# smartstickSTM32f103cb.net
KiCad netlist of a schematic drawn in EAGLE
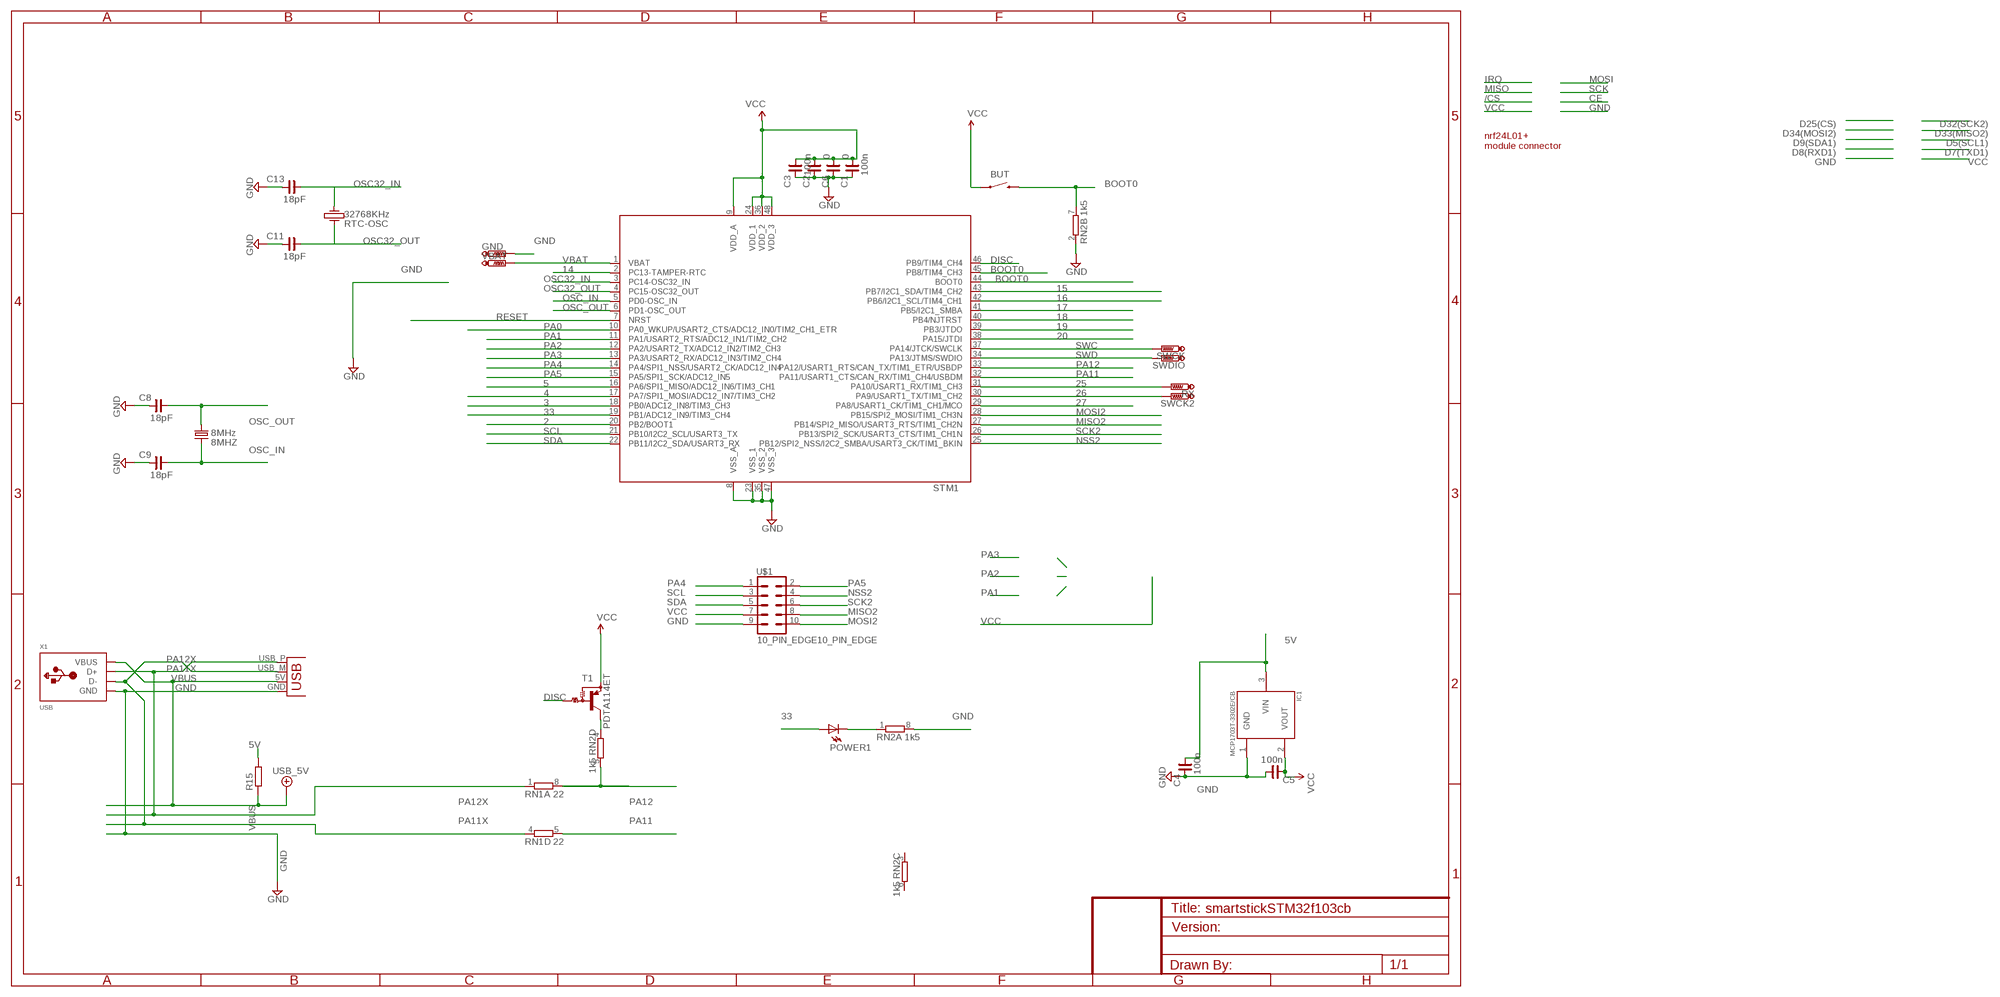
[diagram p0: schematic, sheet 1]

(export (version "E")
  (design (tool "Eeschema 10.0.6"))
  (components
    (comp (ref "8MHZ")
      (value "8MHz")
      (footprint "eagle-import:HC49US")
      (libsource (lib "eagle-import") (part "CRYSTALHC49US"))
    )
    (comp (ref "BUT")
      (value "SWITCH-MOMENTARY-2-SMD-1101NE")
      (footprint "eagle-import:TACTILE-SWITCH-1101NE")
      (libsource (lib "eagle-import") (part "SWITCH-MOMENTARY-2-SMD-1101NE"))
    )
    (comp (ref "C1")
      (value "100n")
      (footprint "eagle-import:C0603")
      (libsource (lib "eagle-import") (part "C_0603"))
    )
    (comp (ref "C2")
      (value "0")
      (footprint "eagle-import:C0603")
      (libsource (lib "eagle-import") (part "C_0603"))
    )
    (comp (ref "C3")
      (value "100n")
      (footprint "eagle-import:C0603")
      (libsource (lib "eagle-import") (part "C_0603"))
    )
    (comp (ref "C4")
      (value "100n")
      (footprint "eagle-import:C0603")
      (libsource (lib "eagle-import") (part "C_0603"))
    )
    (comp (ref "C5")
      (value "100n")
      (footprint "eagle-import:C0603")
      (libsource (lib "eagle-import") (part "C_0603"))
    )
    (comp (ref "C6")
      (value "0")
      (footprint "eagle-import:C0603")
      (libsource (lib "eagle-import") (part "C_0603"))
    )
    (comp (ref "C8")
      (value "18pF")
      (footprint "eagle-import:C0603")
      (libsource (lib "eagle-import") (part "C_0603"))
    )
    (comp (ref "C9")
      (value "18pF")
      (footprint "eagle-import:C0603")
      (libsource (lib "eagle-import") (part "C_0603"))
    )
    (comp (ref "C11")
      (value "18pF")
      (footprint "eagle-import:C0603")
      (libsource (lib "eagle-import") (part "C_0603"))
    )
    (comp (ref "C13")
      (value "18pF")
      (footprint "eagle-import:C0603")
      (libsource (lib "eagle-import") (part "C_0603"))
    )
    (comp (ref "GND")
      (value "PTR1TP20SQ")
      (footprint "eagle-import:TP20SQ")
      (libsource (lib "eagle-import") (part "PTR1TP20SQ"))
    )
    (comp (ref "IC1")
      (value "MCP1703T-3302E/CB")
      (footprint "eagle-import:SOT23")
      (libsource (lib "eagle-import") (part "MCP1700T"))
    )
    (comp (ref "POWER1")
      (value "Power")
      (footprint "eagle-import:LED-0603")
      (libsource (lib "eagle-import") (part "LED0603"))
    )
    (comp (ref "R15")
      (value "R-EU_R0603")
      (footprint "eagle-import:R0603")
      (libsource (lib "eagle-import") (part "R-EU_R0603"))
    )
    (comp (ref "RN1")
      (value "22")
      (footprint "eagle-import:0603-ARC")
      (libsource (lib "eagle-import") (part "4R-N0603-ARC"))
    )
    (comp (ref "RN2")
      (value "1k5")
      (footprint "eagle-import:0603-ARC")
      (libsource (lib "eagle-import") (part "4R-N0603-ARC"))
    )
    (comp (ref "RTC-OSC")
      (value "32768KHz")
      (footprint "eagle-import:KX-327LT")
      (libsource (lib "eagle-import") (part "CRYSTALL"))
    )
    (comp (ref "RX")
      (value "PTR1TP10R")
      (footprint "eagle-import:TP10R")
      (libsource (lib "eagle-import") (part "PTR1TP10R"))
    )
    (comp (ref "STM1")
      (value "STM32F103CB")
      (footprint "eagle-import:LQFP48")
      (libsource (lib "eagle-import") (part "STM32F103CB"))
    )
    (comp (ref "SWCK")
      (value "PTR1TP16R")
      (footprint "eagle-import:TP16R")
      (libsource (lib "eagle-import") (part "PTR1TP16R"))
    )
    (comp (ref "SWCK2")
      (value "PTR1TP10R")
      (footprint "eagle-import:TP10R")
      (libsource (lib "eagle-import") (part "PTR1TP10R"))
    )
    (comp (ref "SWDIO")
      (value "PTR1TP16R")
      (footprint "eagle-import:TP16R")
      (libsource (lib "eagle-import") (part "PTR1TP16R"))
    )
    (comp (ref "T1")
      (value "PDTA114ET")
      (footprint "eagle-import:ES_SOT23-3")
      (libsource (lib "eagle-import") (part "ES_PNP-DRIVERSOT23-3"))
    )
    (comp (ref "U$1")
      (value "10_PIN_EDGE10_PIN_EDGE")
      (footprint "eagle-import:10_PIN_EDGE")
      (libsource (lib "eagle-import") (part "10_PIN_EDGE10_PIN_EDGE"))
    )
    (comp (ref "VBAT")
      (value "PTR1TP19R")
      (footprint "eagle-import:TP19R")
      (libsource (lib "eagle-import") (part "PTR1TP19R"))
    )
    (comp (ref "X1")
      (value "USB")
      (footprint "eagle-import:MOLEX-48037-1000")
      (libsource (lib "eagle-import") (part "USB"))
    )
    (comp (ref "X3")
      (value "USBPCB")
      (footprint "eagle-import:USB-A-PCB")
      (libsource (lib "eagle-import") (part "USBPCB"))
    )
  )
  (nets
    (net (code "1") (name "/2") (class "Default")
      (node (ref "STM1") (pin "20") (pinfunction "PB2/BOOT1_20") (pintype "bidirectional"))
    )
    (net (code "2") (name "/3") (class "Default")
      (node (ref "STM1") (pin "18") (pinfunction "PB0/ADC12_IN8/TIM3_CH3_18") (pintype "bidirectional"))
    )
    (net (code "3") (name "/4") (class "Default")
      (node (ref "STM1") (pin "17") (pinfunction "PA7/SPI1_MOSI/ADC12_IN7/TIM3_CH2_17") (pintype "bidirectional"))
    )
    (net (code "4") (name "/5") (class "Default")
      (node (ref "STM1") (pin "16") (pinfunction "PA6/SPI1_MISO/ADC12_IN6/TIM3_CH1_16") (pintype "bidirectional"))
    )
    (net (code "5") (name "/5V") (class "Default")
      (node (ref "C4") (pin "1") (pinfunction "1_1") (pintype "passive"))
      (node (ref "IC1") (pin "3") (pinfunction "VIN_3") (pintype "bidirectional"))
      (node (ref "R15") (pin "2") (pinfunction "2_2") (pintype "passive"))
    )
    (net (code "6") (name "/14") (class "Default")
      (node (ref "STM1") (pin "2") (pinfunction "PC13-TAMPER-RTC_2") (pintype "input"))
    )
    (net (code "7") (name "/15") (class "Default")
      (node (ref "STM1") (pin "43") (pinfunction "PB7/I2C1_SDA/TIM4_CH2_43") (pintype "bidirectional"))
    )
    (net (code "8") (name "/16") (class "Default")
      (node (ref "STM1") (pin "42") (pinfunction "PB6/I2C1_SCL/TIM4_CH1_42") (pintype "input"))
    )
    (net (code "9") (name "/17") (class "Default")
      (node (ref "STM1") (pin "41") (pinfunction "PB5/I2C1_SMBA_41") (pintype "input"))
    )
    (net (code "10") (name "/18") (class "Default")
      (node (ref "STM1") (pin "40") (pinfunction "PB4/NJTRST_40") (pintype "bidirectional"))
    )
    (net (code "11") (name "/19") (class "Default")
      (node (ref "STM1") (pin "39") (pinfunction "PB3/JTDO_39") (pintype "bidirectional"))
    )
    (net (code "12") (name "/20") (class "Default")
      (node (ref "STM1") (pin "38") (pinfunction "PA15/JTDI_38") (pintype "bidirectional"))
    )
    (net (code "13") (name "/25") (class "Default")
      (node (ref "RX") (pin "TP") (pinfunction "TP_TP") (pintype "input"))
      (node (ref "STM1") (pin "31") (pinfunction "PA10/USART1_RX/TIM1_CH3_31") (pintype "bidirectional"))
    )
    (net (code "14") (name "/26") (class "Default")
      (node (ref "STM1") (pin "30") (pinfunction "PA9/USART1_TX/TIM1_CH2_30") (pintype "input"))
      (node (ref "SWCK2") (pin "TP") (pinfunction "TP_TP") (pintype "input"))
    )
    (net (code "15") (name "/27") (class "Default")
      (node (ref "STM1") (pin "29") (pinfunction "PA8/USART1_CK/TIM1_CH1/MCO_29") (pintype "bidirectional"))
    )
    (net (code "16") (name "/33") (class "Default")
      (node (ref "POWER1") (pin "A") (pinfunction "A_A") (pintype "passive"))
      (node (ref "STM1") (pin "19") (pinfunction "PB1/ADC12_IN9/TIM3_CH4_19") (pintype "bidirectional"))
    )
    (net (code "17") (name "/BOOT0") (class "Default")
      (node (ref "BUT") (pin "P$2") (pinfunction "2_P$2") (pintype "passive"))
      (node (ref "RN2") (pin "7") (pinfunction "2_7") (pintype "passive"))
      (node (ref "STM1") (pin "44") (pinfunction "BOOT0_44") (pintype "input"))
      (node (ref "STM1") (pin "45") (pinfunction "PB8/TIM4_CH3_45") (pintype "bidirectional"))
    )
    (net (code "27") (name "/DISC") (class "Default")
      (node (ref "STM1") (pin "46") (pinfunction "PB9/TIM4_CH4_46") (pintype "input"))
      (node (ref "T1") (pin "1") (pinfunction "B_1") (pintype "passive"))
    )
    (net (code "30") (name "/MISO2") (class "Default")
      (node (ref "STM1") (pin "27") (pinfunction "PB14/SPI2_MISO/USART3_RTS/TIM1_CH2N_27") (pintype "input"))
      (node (ref "U$1") (pin "8") (pinfunction "8_8") (pintype "passive"))
    )
    (net (code "32") (name "/MOSI2") (class "Default")
      (node (ref "STM1") (pin "28") (pinfunction "PB15/SPI2_MOSI/TIM1_CH3N_28") (pintype "input"))
      (node (ref "U$1") (pin "10") (pinfunction "10_10") (pintype "passive"))
    )
    (net (code "33") (name "/NSS2") (class "Default")
      (node (ref "STM1") (pin "25") (pinfunction "PB12/SPI2_NSS/I2C2_SMBA/USART3_CK/TIM1_BKIN_25") (pintype "input"))
      (node (ref "U$1") (pin "4") (pinfunction "4_4") (pintype "passive"))
    )
    (net (code "34") (name "/OSC32_IN") (class "Default")
      (node (ref "C13") (pin "1") (pinfunction "1_1") (pintype "passive"))
      (node (ref "RTC-OSC") (pin "1") (pinfunction "P$1_1") (pintype "bidirectional"))
      (node (ref "STM1") (pin "3") (pinfunction "PC14-OSC32_IN_3") (pintype "input"))
    )
    (net (code "35") (name "/OSC32_OUT") (class "Default")
      (node (ref "C11") (pin "1") (pinfunction "1_1") (pintype "passive"))
      (node (ref "RTC-OSC") (pin "4") (pinfunction "P$2_4") (pintype "bidirectional"))
      (node (ref "STM1") (pin "4") (pinfunction "PC15-OSC32_OUT_4") (pintype "input"))
    )
    (net (code "36") (name "/OSC_IN") (class "Default")
      (node (ref "8MHZ") (pin "2") (pinfunction "2_2") (pintype "passive"))
      (node (ref "C9") (pin "1") (pinfunction "1_1") (pintype "passive"))
      (node (ref "STM1") (pin "5") (pinfunction "PD0-OSC_IN_5") (pintype "input"))
    )
    (net (code "37") (name "/OSC_OUT") (class "Default")
      (node (ref "8MHZ") (pin "1") (pinfunction "1_1") (pintype "passive"))
      (node (ref "C8") (pin "1") (pinfunction "1_1") (pintype "passive"))
      (node (ref "STM1") (pin "6") (pinfunction "PD1-OSC_OUT_6") (pintype "input"))
    )
    (net (code "38") (name "/PA0") (class "Default")
      (node (ref "STM1") (pin "10") (pinfunction "PA0_WKUP/USART2_CTS/ADC12_IN0/TIM2_CH1_ETR_10") (pintype "bidirectional"))
    )
    (net (code "39") (name "/PA1") (class "Default")
      (node (ref "STM1") (pin "11") (pinfunction "PA1/USART2_RTS/ADC12_IN1/TIM2_CH2_11") (pintype "bidirectional"))
    )
    (net (code "40") (name "/PA2") (class "Default")
      (node (ref "STM1") (pin "12") (pinfunction "PA2/USART2_TX/ADC12_IN2/TIM2_CH3_12") (pintype "bidirectional"))
    )
    (net (code "41") (name "/PA3") (class "Default")
      (node (ref "STM1") (pin "13") (pinfunction "PA3/USART2_RX/ADC12_IN3/TIM2_CH4_13") (pintype "bidirectional"))
    )
    (net (code "42") (name "/PA4") (class "Default")
      (node (ref "STM1") (pin "14") (pinfunction "PA4/SPI1_NSS/USART2_CK/ADC12_IN4_14") (pintype "bidirectional"))
      (node (ref "U$1") (pin "1") (pinfunction "1_1") (pintype "passive"))
    )
    (net (code "43") (name "/PA5") (class "Default")
      (node (ref "STM1") (pin "15") (pinfunction "PA5/SPI1_SCK/ADC12_IN5_15") (pintype "bidirectional"))
      (node (ref "U$1") (pin "2") (pinfunction "2_2") (pintype "passive"))
    )
    (net (code "44") (name "/PA11") (class "Default")
      (node (ref "RN1") (pin "5") (pinfunction "2_5") (pintype "passive"))
      (node (ref "STM1") (pin "32") (pinfunction "PA11/USART1_CTS/CAN_RX/TIM1_CH4/USBDM_32") (pintype "bidirectional"))
    )
    (net (code "45") (name "/PA11X") (class "Default")
      (node (ref "RN1") (pin "4") (pinfunction "1_4") (pintype "passive"))
      (node (ref "X1") (pin "2") (pinfunction "D-_2") (pintype "bidirectional"))
      (node (ref "X3") (pin "USB_M") (pinfunction "D-_USB_M") (pintype "bidirectional"))
    )
    (net (code "46") (name "/PA12") (class "Default")
      (node (ref "RN1") (pin "8") (pinfunction "2_8") (pintype "passive"))
      (node (ref "RN2") (pin "5") (pinfunction "2_5") (pintype "passive"))
      (node (ref "STM1") (pin "33") (pinfunction "PA12/USART1_RTS/CAN_TX/TIM1_ETR/USBDP_33") (pintype "bidirectional"))
    )
    (net (code "47") (name "/PA12X") (class "Default")
      (node (ref "RN1") (pin "1") (pinfunction "1_1") (pintype "passive"))
      (node (ref "X1") (pin "3") (pinfunction "D+_3") (pintype "bidirectional"))
      (node (ref "X3") (pin "USB_P") (pinfunction "D+_USB_P") (pintype "bidirectional"))
    )
    (net (code "48") (name "/RESET") (class "Default")
      (node (ref "STM1") (pin "7") (pinfunction "NRST_7") (pintype "input"))
    )
    (net (code "50") (name "/SCK2") (class "Default")
      (node (ref "STM1") (pin "26") (pinfunction "PB13/SPI2_SCK/USART3_CTS/TIM1_CH1N_26") (pintype "input"))
      (node (ref "U$1") (pin "6") (pinfunction "6_6") (pintype "passive"))
    )
    (net (code "51") (name "/SCL") (class "Default")
      (node (ref "STM1") (pin "21") (pinfunction "PB10/I2C2_SCL/USART3_TX_21") (pintype "input"))
      (node (ref "U$1") (pin "3") (pinfunction "3_3") (pintype "passive"))
    )
    (net (code "52") (name "/SDA") (class "Default")
      (node (ref "STM1") (pin "22") (pinfunction "PB11/I2C2_SDA/USART3_RX_22") (pintype "input"))
      (node (ref "U$1") (pin "5") (pinfunction "5_5") (pintype "passive"))
    )
    (net (code "53") (name "/SWC") (class "Default")
      (node (ref "STM1") (pin "37") (pinfunction "PA14/JTCK/SWCLK_37") (pintype "bidirectional"))
      (node (ref "SWCK") (pin "TP") (pinfunction "TP_TP") (pintype "input"))
    )
    (net (code "54") (name "/SWD") (class "Default")
      (node (ref "STM1") (pin "34") (pinfunction "PA13/JTMS/SWDIO_34") (pintype "bidirectional"))
      (node (ref "SWDIO") (pin "TP") (pinfunction "TP_TP") (pintype "input"))
    )
    (net (code "55") (name "/VBAT") (class "Default")
      (node (ref "STM1") (pin "1") (pinfunction "VBAT_1") (pintype "power_in"))
      (node (ref "VBAT") (pin "TP") (pinfunction "TP_TP") (pintype "input"))
    )
    (net (code "57") (name "GND") (class "Default")
      (node (ref "C1") (pin "2") (pinfunction "2_2") (pintype "passive"))
      (node (ref "C11") (pin "2") (pinfunction "2_2") (pintype "passive"))
      (node (ref "C13") (pin "2") (pinfunction "2_2") (pintype "passive"))
      (node (ref "C2") (pin "2") (pinfunction "2_2") (pintype "passive"))
      (node (ref "C3") (pin "2") (pinfunction "2_2") (pintype "passive"))
      (node (ref "C4") (pin "2") (pinfunction "2_2") (pintype "passive"))
      (node (ref "C5") (pin "1") (pinfunction "1_1") (pintype "passive"))
      (node (ref "C6") (pin "2") (pinfunction "2_2") (pintype "passive"))
      (node (ref "C8") (pin "2") (pinfunction "2_2") (pintype "passive"))
      (node (ref "C9") (pin "2") (pinfunction "2_2") (pintype "passive"))
      (node (ref "GND") (pin "TP") (pinfunction "TP_TP") (pintype "input"))
      (node (ref "IC1") (pin "1") (pinfunction "GND_1") (pintype "bidirectional"))
      (node (ref "RN2") (pin "2") (pinfunction "1_2") (pintype "passive"))
      (node (ref "RN2") (pin "8") (pinfunction "2_8") (pintype "passive"))
      (node (ref "STM1") (pin "23") (pinfunction "VSS_1_23") (pintype "power_in"))
      (node (ref "STM1") (pin "35") (pinfunction "VSS_2_35") (pintype "power_in"))
      (node (ref "STM1") (pin "47") (pinfunction "VSS_3_47") (pintype "power_in"))
      (node (ref "STM1") (pin "8") (pinfunction "VSS_A_8") (pintype "power_in"))
      (node (ref "U$1") (pin "9") (pinfunction "9_9") (pintype "passive"))
      (node (ref "X1") (pin "4") (pinfunction "GND_4") (pintype "power_in"))
      (node (ref "X3") (pin "GND") (pinfunction "GND_GND") (pintype "bidirectional"))
    )
    (net (code "58") (name "Net-(POWER1-PadC)") (class "Default")
      (node (ref "POWER1") (pin "C") (pinfunction "C_C") (pintype "passive"))
      (node (ref "RN2") (pin "1") (pinfunction "1_1") (pintype "passive"))
    )
    (net (code "59") (name "Net-(RN2D-1)") (class "Default")
      (node (ref "RN2") (pin "4") (pinfunction "1_4") (pintype "passive"))
      (node (ref "T1") (pin "3") (pinfunction "C_3") (pintype "passive"))
    )
    (net (code "60") (name "USB_5V") (class "Default")
      (node (ref "R15") (pin "1") (pinfunction "1_1") (pintype "passive"))
      (node (ref "X1") (pin "1") (pinfunction "VBUS_1") (pintype "power_in"))
      (node (ref "X3") (pin "5V") (pinfunction "VBUS_5V") (pintype "bidirectional"))
    )
    (net (code "61") (name "VCC") (class "Default")
      (node (ref "BUT") (pin "P$1") (pinfunction "1_P$1") (pintype "passive"))
      (node (ref "C1") (pin "1") (pinfunction "1_1") (pintype "passive"))
      (node (ref "C2") (pin "1") (pinfunction "1_1") (pintype "passive"))
      (node (ref "C3") (pin "1") (pinfunction "1_1") (pintype "passive"))
      (node (ref "C5") (pin "2") (pinfunction "2_2") (pintype "passive"))
      (node (ref "C6") (pin "1") (pinfunction "1_1") (pintype "passive"))
      (node (ref "IC1") (pin "2") (pinfunction "VOUT_2") (pintype "bidirectional"))
      (node (ref "STM1") (pin "24") (pinfunction "VDD_1_24") (pintype "power_in"))
      (node (ref "STM1") (pin "36") (pinfunction "VDD_2_36") (pintype "power_in"))
      (node (ref "STM1") (pin "48") (pinfunction "VDD_3_48") (pintype "power_in"))
      (node (ref "STM1") (pin "9") (pinfunction "VDD_A_9") (pintype "power_in"))
      (node (ref "T1") (pin "2") (pinfunction "E_2") (pintype "passive"))
      (node (ref "U$1") (pin "7") (pinfunction "7_7") (pintype "passive"))
    )
    (net (code "62") (name "unconnected-(RN2C-1-Pad3)") (class "Default")
      (node (ref "RN2") (pin "3") (pinfunction "1_3") (pintype "passive"))
    )
    (net (code "63") (name "unconnected-(RN2C-2-Pad6)") (class "Default")
      (node (ref "RN2") (pin "6") (pinfunction "2_6") (pintype "passive"))
    )
  )
)
